# LEDs.net
KiCad netlist of a schematic drawn in Altium Designer
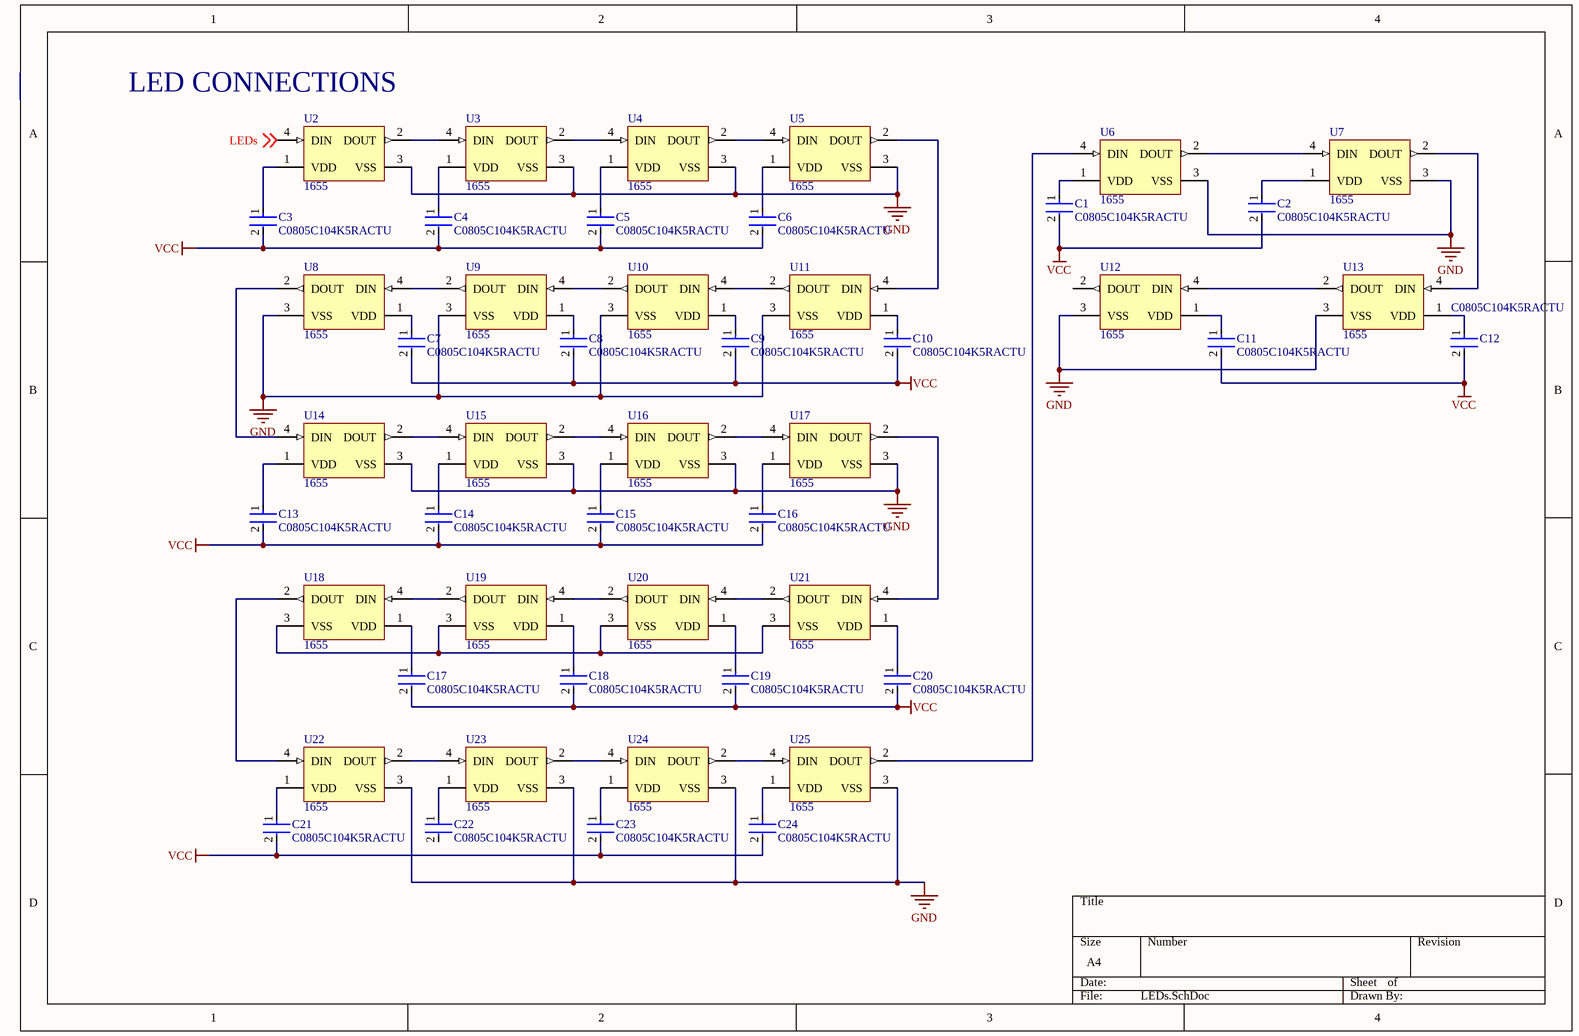
[diagram p0: LEDs.SchDoc]

(export (version "E")
  (design (tool "Eeschema 10.0.6"))
  (components
    (comp (ref "C1")
      (value "C0805C104K5RACTU")
      (footprint "FP-C0805C-DN-MFG")
      (description "CAP CER 0.1UF 50V X7R 0805")
      (fields
        (field (name "MANUFACTURER") "KEMET")
        (field (name "OCTOPART") "https://octopart.com/c0805c104k5ractu-kemet-143926")
      )
      (libsource (lib "Altium Content Vault") (part "b4654b650e69147ec39a6b967a45e02"))
    )
    (comp (ref "C2")
      (value "C0805C104K5RACTU")
      (footprint "FP-C0805C-DN-MFG")
      (description "CAP CER 0.1UF 50V X7R 0805")
      (fields
        (field (name "MANUFACTURER") "KEMET")
        (field (name "OCTOPART") "https://octopart.com/c0805c104k5ractu-kemet-143926")
      )
      (libsource (lib "Altium Content Vault") (part "b4654b650e69147ec39a6b967a45e02"))
    )
    (comp (ref "C3")
      (value "C0805C104K5RACTU")
      (footprint "FP-C0805C-DN-MFG")
      (description "CAP CER 0.1UF 50V X7R 0805")
      (fields
        (field (name "MANUFACTURER") "KEMET")
        (field (name "OCTOPART") "https://octopart.com/c0805c104k5ractu-kemet-143926")
      )
      (libsource (lib "Altium Content Vault") (part "b4654b650e69147ec39a6b967a45e02"))
    )
    (comp (ref "C4")
      (value "C0805C104K5RACTU")
      (footprint "FP-C0805C-DN-MFG")
      (description "CAP CER 0.1UF 50V X7R 0805")
      (fields
        (field (name "MANUFACTURER") "KEMET")
        (field (name "OCTOPART") "https://octopart.com/c0805c104k5ractu-kemet-143926")
      )
      (libsource (lib "Altium Content Vault") (part "b4654b650e69147ec39a6b967a45e02"))
    )
    (comp (ref "C5")
      (value "C0805C104K5RACTU")
      (footprint "FP-C0805C-DN-MFG")
      (description "CAP CER 0.1UF 50V X7R 0805")
      (fields
        (field (name "MANUFACTURER") "KEMET")
        (field (name "OCTOPART") "https://octopart.com/c0805c104k5ractu-kemet-143926")
      )
      (libsource (lib "Altium Content Vault") (part "b4654b650e69147ec39a6b967a45e02"))
    )
    (comp (ref "C6")
      (value "C0805C104K5RACTU")
      (footprint "FP-C0805C-DN-MFG")
      (description "CAP CER 0.1UF 50V X7R 0805")
      (fields
        (field (name "MANUFACTURER") "KEMET")
        (field (name "OCTOPART") "https://octopart.com/c0805c104k5ractu-kemet-143926")
      )
      (libsource (lib "Altium Content Vault") (part "b4654b650e69147ec39a6b967a45e02"))
    )
    (comp (ref "C7")
      (value "C0805C104K5RACTU")
      (footprint "FP-C0805C-DN-MFG")
      (description "CAP CER 0.1UF 50V X7R 0805")
      (fields
        (field (name "MANUFACTURER") "KEMET")
        (field (name "OCTOPART") "https://octopart.com/c0805c104k5ractu-kemet-143926")
      )
      (libsource (lib "Altium Content Vault") (part "b4654b650e69147ec39a6b967a45e02"))
    )
    (comp (ref "C8")
      (value "C0805C104K5RACTU")
      (footprint "FP-C0805C-DN-MFG")
      (description "CAP CER 0.1UF 50V X7R 0805")
      (fields
        (field (name "MANUFACTURER") "KEMET")
        (field (name "OCTOPART") "https://octopart.com/c0805c104k5ractu-kemet-143926")
      )
      (libsource (lib "Altium Content Vault") (part "b4654b650e69147ec39a6b967a45e02"))
    )
    (comp (ref "C9")
      (value "C0805C104K5RACTU")
      (footprint "FP-C0805C-DN-MFG")
      (description "CAP CER 0.1UF 50V X7R 0805")
      (fields
        (field (name "MANUFACTURER") "KEMET")
        (field (name "OCTOPART") "https://octopart.com/c0805c104k5ractu-kemet-143926")
      )
      (libsource (lib "Altium Content Vault") (part "b4654b650e69147ec39a6b967a45e02"))
    )
    (comp (ref "C10")
      (value "C0805C104K5RACTU")
      (footprint "FP-C0805C-DN-MFG")
      (description "CAP CER 0.1UF 50V X7R 0805")
      (fields
        (field (name "MANUFACTURER") "KEMET")
        (field (name "OCTOPART") "https://octopart.com/c0805c104k5ractu-kemet-143926")
      )
      (libsource (lib "Altium Content Vault") (part "b4654b650e69147ec39a6b967a45e02"))
    )
    (comp (ref "C11")
      (value "C0805C104K5RACTU")
      (footprint "FP-C0805C-DN-MFG")
      (description "CAP CER 0.1UF 50V X7R 0805")
      (fields
        (field (name "MANUFACTURER") "KEMET")
        (field (name "OCTOPART") "https://octopart.com/c0805c104k5ractu-kemet-143926")
      )
      (libsource (lib "Altium Content Vault") (part "b4654b650e69147ec39a6b967a45e02"))
    )
    (comp (ref "C12")
      (value "C0805C104K5RACTU")
      (footprint "FP-C0805C-DN-MFG")
      (description "CAP CER 0.1UF 50V X7R 0805")
      (fields
        (field (name "MANUFACTURER") "KEMET")
        (field (name "OCTOPART") "https://octopart.com/c0805c104k5ractu-kemet-143926")
      )
      (libsource (lib "Altium Content Vault") (part "b4654b650e69147ec39a6b967a45e02"))
    )
    (comp (ref "C13")
      (value "C0805C104K5RACTU")
      (footprint "FP-C0805C-DN-MFG")
      (description "CAP CER 0.1UF 50V X7R 0805")
      (fields
        (field (name "MANUFACTURER") "KEMET")
        (field (name "OCTOPART") "https://octopart.com/c0805c104k5ractu-kemet-143926")
      )
      (libsource (lib "Altium Content Vault") (part "b4654b650e69147ec39a6b967a45e02"))
    )
    (comp (ref "C14")
      (value "C0805C104K5RACTU")
      (footprint "FP-C0805C-DN-MFG")
      (description "CAP CER 0.1UF 50V X7R 0805")
      (fields
        (field (name "MANUFACTURER") "KEMET")
        (field (name "OCTOPART") "https://octopart.com/c0805c104k5ractu-kemet-143926")
      )
      (libsource (lib "Altium Content Vault") (part "b4654b650e69147ec39a6b967a45e02"))
    )
    (comp (ref "C15")
      (value "C0805C104K5RACTU")
      (footprint "FP-C0805C-DN-MFG")
      (description "CAP CER 0.1UF 50V X7R 0805")
      (fields
        (field (name "MANUFACTURER") "KEMET")
        (field (name "OCTOPART") "https://octopart.com/c0805c104k5ractu-kemet-143926")
      )
      (libsource (lib "Altium Content Vault") (part "b4654b650e69147ec39a6b967a45e02"))
    )
    (comp (ref "C16")
      (value "C0805C104K5RACTU")
      (footprint "FP-C0805C-DN-MFG")
      (description "CAP CER 0.1UF 50V X7R 0805")
      (fields
        (field (name "MANUFACTURER") "KEMET")
        (field (name "OCTOPART") "https://octopart.com/c0805c104k5ractu-kemet-143926")
      )
      (libsource (lib "Altium Content Vault") (part "b4654b650e69147ec39a6b967a45e02"))
    )
    (comp (ref "C17")
      (value "C0805C104K5RACTU")
      (footprint "FP-C0805C-DN-MFG")
      (description "CAP CER 0.1UF 50V X7R 0805")
      (fields
        (field (name "MANUFACTURER") "KEMET")
        (field (name "OCTOPART") "https://octopart.com/c0805c104k5ractu-kemet-143926")
      )
      (libsource (lib "Altium Content Vault") (part "b4654b650e69147ec39a6b967a45e02"))
    )
    (comp (ref "C18")
      (value "C0805C104K5RACTU")
      (footprint "FP-C0805C-DN-MFG")
      (description "CAP CER 0.1UF 50V X7R 0805")
      (fields
        (field (name "MANUFACTURER") "KEMET")
        (field (name "OCTOPART") "https://octopart.com/c0805c104k5ractu-kemet-143926")
      )
      (libsource (lib "Altium Content Vault") (part "b4654b650e69147ec39a6b967a45e02"))
    )
    (comp (ref "C19")
      (value "C0805C104K5RACTU")
      (footprint "FP-C0805C-DN-MFG")
      (description "CAP CER 0.1UF 50V X7R 0805")
      (fields
        (field (name "MANUFACTURER") "KEMET")
        (field (name "OCTOPART") "https://octopart.com/c0805c104k5ractu-kemet-143926")
      )
      (libsource (lib "Altium Content Vault") (part "b4654b650e69147ec39a6b967a45e02"))
    )
    (comp (ref "C20")
      (value "C0805C104K5RACTU")
      (footprint "FP-C0805C-DN-MFG")
      (description "CAP CER 0.1UF 50V X7R 0805")
      (fields
        (field (name "MANUFACTURER") "KEMET")
        (field (name "OCTOPART") "https://octopart.com/c0805c104k5ractu-kemet-143926")
      )
      (libsource (lib "Altium Content Vault") (part "b4654b650e69147ec39a6b967a45e02"))
    )
    (comp (ref "C21")
      (value "C0805C104K5RACTU")
      (footprint "FP-C0805C-DN-MFG")
      (description "CAP CER 0.1UF 50V X7R 0805")
      (fields
        (field (name "MANUFACTURER") "KEMET")
        (field (name "OCTOPART") "https://octopart.com/c0805c104k5ractu-kemet-143926")
      )
      (libsource (lib "Altium Content Vault") (part "b4654b650e69147ec39a6b967a45e02"))
    )
    (comp (ref "C22")
      (value "C0805C104K5RACTU")
      (footprint "FP-C0805C-DN-MFG")
      (description "CAP CER 0.1UF 50V X7R 0805")
      (fields
        (field (name "MANUFACTURER") "KEMET")
        (field (name "OCTOPART") "https://octopart.com/c0805c104k5ractu-kemet-143926")
      )
      (libsource (lib "Altium Content Vault") (part "b4654b650e69147ec39a6b967a45e02"))
    )
    (comp (ref "C23")
      (value "C0805C104K5RACTU")
      (footprint "FP-C0805C-DN-MFG")
      (description "CAP CER 0.1UF 50V X7R 0805")
      (fields
        (field (name "MANUFACTURER") "KEMET")
        (field (name "OCTOPART") "https://octopart.com/c0805c104k5ractu-kemet-143926")
      )
      (libsource (lib "Altium Content Vault") (part "b4654b650e69147ec39a6b967a45e02"))
    )
    (comp (ref "C24")
      (value "C0805C104K5RACTU")
      (footprint "FP-C0805C-DN-MFG")
      (description "CAP CER 0.1UF 50V X7R 0805")
      (fields
        (field (name "MANUFACTURER") "KEMET")
        (field (name "OCTOPART") "https://octopart.com/c0805c104k5ractu-kemet-143926")
      )
      (libsource (lib "Altium Content Vault") (part "b4654b650e69147ec39a6b967a45e02"))
    )
    (comp (ref "U2")
      (value "1655")
      (footprint "ADA-RGB-1655_V")
      (fields (field (name "MANUFACTURER") "Adafruit-Industries-LLC"))
      (libsource (lib "Altium Content Vault") (part "ADA-RGB-1655-4"))
    )
    (comp (ref "U3")
      (value "1655")
      (footprint "ADA-RGB-1655_V")
      (fields (field (name "MANUFACTURER") "Adafruit-Industries-LLC"))
      (libsource (lib "Altium Content Vault") (part "ADA-RGB-1655-4"))
    )
    (comp (ref "U4")
      (value "1655")
      (footprint "ADA-RGB-1655_V")
      (fields (field (name "MANUFACTURER") "Adafruit-Industries-LLC"))
      (libsource (lib "Altium Content Vault") (part "ADA-RGB-1655-4"))
    )
    (comp (ref "U5")
      (value "1655")
      (footprint "ADA-RGB-1655_V")
      (fields (field (name "MANUFACTURER") "Adafruit-Industries-LLC"))
      (libsource (lib "Altium Content Vault") (part "ADA-RGB-1655-4"))
    )
    (comp (ref "U6")
      (value "1655")
      (footprint "ADA-RGB-1655_V")
      (fields (field (name "MANUFACTURER") "Adafruit-Industries-LLC"))
      (libsource (lib "Altium Content Vault") (part "ADA-RGB-1655-4"))
    )
    (comp (ref "U7")
      (value "1655")
      (footprint "ADA-RGB-1655_V")
      (fields (field (name "MANUFACTURER") "Adafruit-Industries-LLC"))
      (libsource (lib "Altium Content Vault") (part "ADA-RGB-1655-4"))
    )
    (comp (ref "U8")
      (value "1655")
      (footprint "ADA-RGB-1655_V")
      (fields (field (name "MANUFACTURER") "Adafruit-Industries-LLC"))
      (libsource (lib "") (part "ADA-RGB-1655-4_1"))
    )
    (comp (ref "U9")
      (value "1655")
      (footprint "ADA-RGB-1655_V")
      (fields (field (name "MANUFACTURER") "Adafruit-Industries-LLC"))
      (libsource (lib "") (part "ADA-RGB-1655-4_1"))
    )
    (comp (ref "U10")
      (value "1655")
      (footprint "ADA-RGB-1655_V")
      (fields (field (name "MANUFACTURER") "Adafruit-Industries-LLC"))
      (libsource (lib "") (part "ADA-RGB-1655-4_1"))
    )
    (comp (ref "U11")
      (value "1655")
      (footprint "ADA-RGB-1655_V")
      (fields (field (name "MANUFACTURER") "Adafruit-Industries-LLC"))
      (libsource (lib "") (part "ADA-RGB-1655-4_1"))
    )
    (comp (ref "U12")
      (value "1655")
      (footprint "ADA-RGB-1655_V")
      (fields (field (name "MANUFACTURER") "Adafruit-Industries-LLC"))
      (libsource (lib "") (part "ADA-RGB-1655-4_1"))
    )
    (comp (ref "U13")
      (value "1655")
      (footprint "ADA-RGB-1655_V")
      (fields (field (name "MANUFACTURER") "Adafruit-Industries-LLC"))
      (libsource (lib "") (part "ADA-RGB-1655-4_1"))
    )
    (comp (ref "U14")
      (value "1655")
      (footprint "ADA-RGB-1655_V")
      (fields (field (name "MANUFACTURER") "Adafruit-Industries-LLC"))
      (libsource (lib "Altium Content Vault") (part "ADA-RGB-1655-4"))
    )
    (comp (ref "U15")
      (value "1655")
      (footprint "ADA-RGB-1655_V")
      (fields (field (name "MANUFACTURER") "Adafruit-Industries-LLC"))
      (libsource (lib "Altium Content Vault") (part "ADA-RGB-1655-4"))
    )
    (comp (ref "U16")
      (value "1655")
      (footprint "ADA-RGB-1655_V")
      (fields (field (name "MANUFACTURER") "Adafruit-Industries-LLC"))
      (libsource (lib "Altium Content Vault") (part "ADA-RGB-1655-4"))
    )
    (comp (ref "U17")
      (value "1655")
      (footprint "ADA-RGB-1655_V")
      (fields (field (name "MANUFACTURER") "Adafruit-Industries-LLC"))
      (libsource (lib "Altium Content Vault") (part "ADA-RGB-1655-4"))
    )
    (comp (ref "U18")
      (value "1655")
      (footprint "ADA-RGB-1655_V")
      (fields (field (name "MANUFACTURER") "Adafruit-Industries-LLC"))
      (libsource (lib "") (part "ADA-RGB-1655-4_1"))
    )
    (comp (ref "U19")
      (value "1655")
      (footprint "ADA-RGB-1655_V")
      (fields (field (name "MANUFACTURER") "Adafruit-Industries-LLC"))
      (libsource (lib "") (part "ADA-RGB-1655-4_1"))
    )
    (comp (ref "U20")
      (value "1655")
      (footprint "ADA-RGB-1655_V")
      (fields (field (name "MANUFACTURER") "Adafruit-Industries-LLC"))
      (libsource (lib "") (part "ADA-RGB-1655-4_1"))
    )
    (comp (ref "U21")
      (value "1655")
      (footprint "ADA-RGB-1655_V")
      (fields (field (name "MANUFACTURER") "Adafruit-Industries-LLC"))
      (libsource (lib "") (part "ADA-RGB-1655-4_1"))
    )
    (comp (ref "U22")
      (value "1655")
      (footprint "ADA-RGB-1655_V")
      (fields (field (name "MANUFACTURER") "Adafruit-Industries-LLC"))
      (libsource (lib "Altium Content Vault") (part "ADA-RGB-1655-4"))
    )
    (comp (ref "U23")
      (value "1655")
      (footprint "ADA-RGB-1655_V")
      (fields (field (name "MANUFACTURER") "Adafruit-Industries-LLC"))
      (libsource (lib "Altium Content Vault") (part "ADA-RGB-1655-4"))
    )
    (comp (ref "U24")
      (value "1655")
      (footprint "ADA-RGB-1655_V")
      (fields (field (name "MANUFACTURER") "Adafruit-Industries-LLC"))
      (libsource (lib "Altium Content Vault") (part "ADA-RGB-1655-4"))
    )
    (comp (ref "U25")
      (value "1655")
      (footprint "ADA-RGB-1655_V")
      (fields (field (name "MANUFACTURER") "Adafruit-Industries-LLC"))
      (libsource (lib "Altium Content Vault") (part "ADA-RGB-1655-4"))
    )
  )
  (nets
    (net (code "1") (name "GND") (class "Default")
      (node (ref "U10") (pin "3") (pinfunction "VSS_3") (pintype "power_in"))
      (node (ref "U11") (pin "3") (pinfunction "VSS_3") (pintype "power_in"))
      (node (ref "U12") (pin "3") (pinfunction "VSS_3") (pintype "power_in"))
      (node (ref "U13") (pin "3") (pinfunction "VSS_3") (pintype "power_in"))
      (node (ref "U14") (pin "3") (pinfunction "VSS_3") (pintype "power_in"))
      (node (ref "U15") (pin "3") (pinfunction "VSS_3") (pintype "power_in"))
      (node (ref "U16") (pin "3") (pinfunction "VSS_3") (pintype "power_in"))
      (node (ref "U17") (pin "3") (pinfunction "VSS_3") (pintype "power_in"))
      (node (ref "U2") (pin "3") (pinfunction "VSS_3") (pintype "power_in"))
      (node (ref "U22") (pin "3") (pinfunction "VSS_3") (pintype "power_in"))
      (node (ref "U23") (pin "3") (pinfunction "VSS_3") (pintype "power_in"))
      (node (ref "U24") (pin "3") (pinfunction "VSS_3") (pintype "power_in"))
      (node (ref "U25") (pin "3") (pinfunction "VSS_3") (pintype "power_in"))
      (node (ref "U3") (pin "3") (pinfunction "VSS_3") (pintype "power_in"))
      (node (ref "U4") (pin "3") (pinfunction "VSS_3") (pintype "power_in"))
      (node (ref "U5") (pin "3") (pinfunction "VSS_3") (pintype "power_in"))
      (node (ref "U6") (pin "3") (pinfunction "VSS_3") (pintype "power_in"))
      (node (ref "U7") (pin "3") (pinfunction "VSS_3") (pintype "power_in"))
      (node (ref "U8") (pin "3") (pinfunction "VSS_3") (pintype "power_in"))
      (node (ref "U9") (pin "3") (pinfunction "VSS_3") (pintype "power_in"))
    )
    (net (code "2") (name "LEDs") (class "Default")
      (node (ref "U2") (pin "4") (pinfunction "DIN_4") (pintype "input"))
    )
    (net (code "3") (name "Net-(U2-DOUT)") (class "Default")
      (node (ref "U2") (pin "2") (pinfunction "DOUT_2") (pintype "output"))
      (node (ref "U3") (pin "4") (pinfunction "DIN_4") (pintype "input"))
    )
    (net (code "4") (name "Net-(U2-VDD)") (class "Default")
      (node (ref "C3") (pin "1") (pinfunction "1_1") (pintype "passive"))
      (node (ref "U2") (pin "1") (pinfunction "VDD_1") (pintype "power_in"))
    )
    (net (code "5") (name "Net-(U3-DOUT)") (class "Default")
      (node (ref "U3") (pin "2") (pinfunction "DOUT_2") (pintype "output"))
      (node (ref "U4") (pin "4") (pinfunction "DIN_4") (pintype "input"))
    )
    (net (code "6") (name "Net-(U3-VDD)") (class "Default")
      (node (ref "C4") (pin "1") (pinfunction "1_1") (pintype "passive"))
      (node (ref "U3") (pin "1") (pinfunction "VDD_1") (pintype "power_in"))
    )
    (net (code "7") (name "Net-(U4-DOUT)") (class "Default")
      (node (ref "U4") (pin "2") (pinfunction "DOUT_2") (pintype "output"))
      (node (ref "U5") (pin "4") (pinfunction "DIN_4") (pintype "input"))
    )
    (net (code "8") (name "Net-(U4-VDD)") (class "Default")
      (node (ref "C5") (pin "1") (pinfunction "1_1") (pintype "passive"))
      (node (ref "U4") (pin "1") (pinfunction "VDD_1") (pintype "power_in"))
    )
    (net (code "9") (name "Net-(U5-VDD)") (class "Default")
      (node (ref "C6") (pin "1") (pinfunction "1_1") (pintype "passive"))
      (node (ref "U5") (pin "1") (pinfunction "VDD_1") (pintype "power_in"))
    )
    (net (code "10") (name "Net-(U6-DOUT)") (class "Default")
      (node (ref "U6") (pin "2") (pinfunction "DOUT_2") (pintype "output"))
      (node (ref "U7") (pin "4") (pinfunction "DIN_4") (pintype "input"))
    )
    (net (code "11") (name "Net-(U6-VDD)") (class "Default")
      (node (ref "C1") (pin "1") (pinfunction "1_1") (pintype "passive"))
      (node (ref "U6") (pin "1") (pinfunction "VDD_1") (pintype "power_in"))
    )
    (net (code "12") (name "Net-(U7-VDD)") (class "Default")
      (node (ref "C2") (pin "1") (pinfunction "1_1") (pintype "passive"))
      (node (ref "U7") (pin "1") (pinfunction "VDD_1") (pintype "power_in"))
    )
    (net (code "13") (name "Net-(U8-DIN)") (class "Default")
      (node (ref "U8") (pin "4") (pinfunction "DIN_4") (pintype "input"))
      (node (ref "U9") (pin "2") (pinfunction "DOUT_2") (pintype "output"))
    )
    (net (code "14") (name "Net-(U8-VDD)") (class "Default")
      (node (ref "C7") (pin "1") (pinfunction "1_1") (pintype "passive"))
      (node (ref "U8") (pin "1") (pinfunction "VDD_1") (pintype "power_in"))
    )
    (net (code "15") (name "Net-(U9-VDD)") (class "Default")
      (node (ref "C8") (pin "1") (pinfunction "1_1") (pintype "passive"))
      (node (ref "U9") (pin "1") (pinfunction "VDD_1") (pintype "power_in"))
    )
    (net (code "16") (name "Net-(U10-DIN)") (class "Default")
      (node (ref "U10") (pin "4") (pinfunction "DIN_4") (pintype "input"))
      (node (ref "U11") (pin "2") (pinfunction "DOUT_2") (pintype "output"))
    )
    (net (code "17") (name "Net-(U10-DOUT)") (class "Default")
      (node (ref "U10") (pin "2") (pinfunction "DOUT_2") (pintype "output"))
      (node (ref "U9") (pin "4") (pinfunction "DIN_4") (pintype "input"))
    )
    (net (code "18") (name "Net-(U10-VDD)") (class "Default")
      (node (ref "C9") (pin "1") (pinfunction "1_1") (pintype "passive"))
      (node (ref "U10") (pin "1") (pinfunction "VDD_1") (pintype "power_in"))
    )
    (net (code "19") (name "Net-(U11-DIN)") (class "Default")
      (node (ref "U11") (pin "4") (pinfunction "DIN_4") (pintype "input"))
      (node (ref "U5") (pin "2") (pinfunction "DOUT_2") (pintype "output"))
    )
    (net (code "20") (name "Net-(U11-VDD)") (class "Default")
      (node (ref "C10") (pin "1") (pinfunction "1_1") (pintype "passive"))
      (node (ref "U11") (pin "1") (pinfunction "VDD_1") (pintype "power_in"))
    )
    (net (code "21") (name "Net-(U12-DIN)") (class "Default")
      (node (ref "U12") (pin "4") (pinfunction "DIN_4") (pintype "input"))
      (node (ref "U13") (pin "2") (pinfunction "DOUT_2") (pintype "output"))
    )
    (net (code "22") (name "Net-(U12-VDD)") (class "Default")
      (node (ref "C11") (pin "1") (pinfunction "1_1") (pintype "passive"))
      (node (ref "U12") (pin "1") (pinfunction "VDD_1") (pintype "power_in"))
    )
    (net (code "23") (name "Net-(U13-DIN)") (class "Default")
      (node (ref "U13") (pin "4") (pinfunction "DIN_4") (pintype "input"))
      (node (ref "U7") (pin "2") (pinfunction "DOUT_2") (pintype "output"))
    )
    (net (code "24") (name "Net-(U13-VDD)") (class "Default")
      (node (ref "C12") (pin "1") (pinfunction "1_1") (pintype "passive"))
      (node (ref "U13") (pin "1") (pinfunction "VDD_1") (pintype "power_in"))
    )
    (net (code "25") (name "Net-(U14-DIN)") (class "Default")
      (node (ref "U14") (pin "4") (pinfunction "DIN_4") (pintype "input"))
      (node (ref "U8") (pin "2") (pinfunction "DOUT_2") (pintype "output"))
    )
    (net (code "26") (name "Net-(U14-DOUT)") (class "Default")
      (node (ref "U14") (pin "2") (pinfunction "DOUT_2") (pintype "output"))
      (node (ref "U15") (pin "4") (pinfunction "DIN_4") (pintype "input"))
    )
    (net (code "27") (name "Net-(U14-VDD)") (class "Default")
      (node (ref "C13") (pin "1") (pinfunction "1_1") (pintype "passive"))
      (node (ref "U14") (pin "1") (pinfunction "VDD_1") (pintype "power_in"))
    )
    (net (code "28") (name "Net-(U15-DOUT)") (class "Default")
      (node (ref "U15") (pin "2") (pinfunction "DOUT_2") (pintype "output"))
      (node (ref "U16") (pin "4") (pinfunction "DIN_4") (pintype "input"))
    )
    (net (code "29") (name "Net-(U15-VDD)") (class "Default")
      (node (ref "C14") (pin "1") (pinfunction "1_1") (pintype "passive"))
      (node (ref "U15") (pin "1") (pinfunction "VDD_1") (pintype "power_in"))
    )
    (net (code "30") (name "Net-(U16-DOUT)") (class "Default")
      (node (ref "U16") (pin "2") (pinfunction "DOUT_2") (pintype "output"))
      (node (ref "U17") (pin "4") (pinfunction "DIN_4") (pintype "input"))
    )
    (net (code "31") (name "Net-(U16-VDD)") (class "Default")
      (node (ref "C15") (pin "1") (pinfunction "1_1") (pintype "passive"))
      (node (ref "U16") (pin "1") (pinfunction "VDD_1") (pintype "power_in"))
    )
    (net (code "32") (name "Net-(U17-DOUT)") (class "Default")
      (node (ref "U17") (pin "2") (pinfunction "DOUT_2") (pintype "output"))
      (node (ref "U21") (pin "4") (pinfunction "DIN_4") (pintype "input"))
    )
    (net (code "33") (name "Net-(U17-VDD)") (class "Default")
      (node (ref "C16") (pin "1") (pinfunction "1_1") (pintype "passive"))
      (node (ref "U17") (pin "1") (pinfunction "VDD_1") (pintype "power_in"))
    )
    (net (code "34") (name "Net-(U18-DIN)") (class "Default")
      (node (ref "U18") (pin "4") (pinfunction "DIN_4") (pintype "input"))
      (node (ref "U19") (pin "2") (pinfunction "DOUT_2") (pintype "output"))
    )
    (net (code "35") (name "Net-(U18-DOUT)") (class "Default")
      (node (ref "U18") (pin "2") (pinfunction "DOUT_2") (pintype "output"))
      (node (ref "U22") (pin "4") (pinfunction "DIN_4") (pintype "input"))
    )
    (net (code "36") (name "Net-(U18-VDD)") (class "Default")
      (node (ref "C17") (pin "1") (pinfunction "1_1") (pintype "passive"))
      (node (ref "U18") (pin "1") (pinfunction "VDD_1") (pintype "power_in"))
    )
    (net (code "37") (name "Net-(U18-VSS)") (class "Default")
      (node (ref "U18") (pin "3") (pinfunction "VSS_3") (pintype "power_in"))
      (node (ref "U19") (pin "3") (pinfunction "VSS_3") (pintype "power_in"))
      (node (ref "U20") (pin "3") (pinfunction "VSS_3") (pintype "power_in"))
      (node (ref "U21") (pin "3") (pinfunction "VSS_3") (pintype "power_in"))
    )
    (net (code "38") (name "Net-(U19-DIN)") (class "Default")
      (node (ref "U19") (pin "4") (pinfunction "DIN_4") (pintype "input"))
      (node (ref "U20") (pin "2") (pinfunction "DOUT_2") (pintype "output"))
    )
    (net (code "39") (name "Net-(U19-VDD)") (class "Default")
      (node (ref "C18") (pin "1") (pinfunction "1_1") (pintype "passive"))
      (node (ref "U19") (pin "1") (pinfunction "VDD_1") (pintype "power_in"))
    )
    (net (code "40") (name "Net-(U20-DIN)") (class "Default")
      (node (ref "U20") (pin "4") (pinfunction "DIN_4") (pintype "input"))
      (node (ref "U21") (pin "2") (pinfunction "DOUT_2") (pintype "output"))
    )
    (net (code "41") (name "Net-(U20-VDD)") (class "Default")
      (node (ref "C19") (pin "1") (pinfunction "1_1") (pintype "passive"))
      (node (ref "U20") (pin "1") (pinfunction "VDD_1") (pintype "power_in"))
    )
    (net (code "42") (name "Net-(U21-VDD)") (class "Default")
      (node (ref "C20") (pin "1") (pinfunction "1_1") (pintype "passive"))
      (node (ref "U21") (pin "1") (pinfunction "VDD_1") (pintype "power_in"))
    )
    (net (code "43") (name "Net-(U22-DOUT)") (class "Default")
      (node (ref "U22") (pin "2") (pinfunction "DOUT_2") (pintype "output"))
      (node (ref "U23") (pin "4") (pinfunction "DIN_4") (pintype "input"))
    )
    (net (code "44") (name "Net-(U22-VDD)") (class "Default")
      (node (ref "C21") (pin "1") (pinfunction "1_1") (pintype "passive"))
      (node (ref "U22") (pin "1") (pinfunction "VDD_1") (pintype "power_in"))
    )
    (net (code "45") (name "Net-(U23-DOUT)") (class "Default")
      (node (ref "U23") (pin "2") (pinfunction "DOUT_2") (pintype "output"))
      (node (ref "U24") (pin "4") (pinfunction "DIN_4") (pintype "input"))
    )
    (net (code "46") (name "Net-(U23-VDD)") (class "Default")
      (node (ref "C22") (pin "1") (pinfunction "1_1") (pintype "passive"))
      (node (ref "U23") (pin "1") (pinfunction "VDD_1") (pintype "power_in"))
    )
    (net (code "47") (name "Net-(U24-DOUT)") (class "Default")
      (node (ref "U24") (pin "2") (pinfunction "DOUT_2") (pintype "output"))
      (node (ref "U25") (pin "4") (pinfunction "DIN_4") (pintype "input"))
    )
    (net (code "48") (name "Net-(U24-VDD)") (class "Default")
      (node (ref "C23") (pin "1") (pinfunction "1_1") (pintype "passive"))
      (node (ref "U24") (pin "1") (pinfunction "VDD_1") (pintype "power_in"))
    )
    (net (code "49") (name "Net-(U25-DOUT)") (class "Default")
      (node (ref "U25") (pin "2") (pinfunction "DOUT_2") (pintype "output"))
      (node (ref "U6") (pin "4") (pinfunction "DIN_4") (pintype "input"))
    )
    (net (code "50") (name "Net-(U25-VDD)") (class "Default")
      (node (ref "C24") (pin "1") (pinfunction "1_1") (pintype "passive"))
      (node (ref "U25") (pin "1") (pinfunction "VDD_1") (pintype "power_in"))
    )
    (net (code "51") (name "VCC") (class "Default")
      (node (ref "C1") (pin "2") (pinfunction "2_2") (pintype "passive"))
      (node (ref "C10") (pin "2") (pinfunction "2_2") (pintype "passive"))
      (node (ref "C11") (pin "2") (pinfunction "2_2") (pintype "passive"))
      (node (ref "C12") (pin "2") (pinfunction "2_2") (pintype "passive"))
      (node (ref "C13") (pin "2") (pinfunction "2_2") (pintype "passive"))
      (node (ref "C14") (pin "2") (pinfunction "2_2") (pintype "passive"))
      (node (ref "C15") (pin "2") (pinfunction "2_2") (pintype "passive"))
      (node (ref "C16") (pin "2") (pinfunction "2_2") (pintype "passive"))
      (node (ref "C17") (pin "2") (pinfunction "2_2") (pintype "passive"))
      (node (ref "C18") (pin "2") (pinfunction "2_2") (pintype "passive"))
      (node (ref "C19") (pin "2") (pinfunction "2_2") (pintype "passive"))
      (node (ref "C2") (pin "2") (pinfunction "2_2") (pintype "passive"))
      (node (ref "C20") (pin "2") (pinfunction "2_2") (pintype "passive"))
      (node (ref "C21") (pin "2") (pinfunction "2_2") (pintype "passive"))
      (node (ref "C23") (pin "2") (pinfunction "2_2") (pintype "passive"))
      (node (ref "C24") (pin "2") (pinfunction "2_2") (pintype "passive"))
      (node (ref "C3") (pin "2") (pinfunction "2_2") (pintype "passive"))
      (node (ref "C4") (pin "2") (pinfunction "2_2") (pintype "passive"))
      (node (ref "C5") (pin "2") (pinfunction "2_2") (pintype "passive"))
      (node (ref "C6") (pin "2") (pinfunction "2_2") (pintype "passive"))
      (node (ref "C7") (pin "2") (pinfunction "2_2") (pintype "passive"))
      (node (ref "C8") (pin "2") (pinfunction "2_2") (pintype "passive"))
      (node (ref "C9") (pin "2") (pinfunction "2_2") (pintype "passive"))
    )
    (net (code "52") (name "unconnected-(C22-Pad2)") (class "Default")
      (node (ref "C22") (pin "2") (pinfunction "2_2") (pintype "passive"))
    )
    (net (code "53") (name "unconnected-(U12-DOUT-Pad2)") (class "Default")
      (node (ref "U12") (pin "2") (pinfunction "DOUT_2") (pintype "output"))
    )
  )
)
